# POWER.net
KiCad netlist of a schematic drawn in Altium Designer
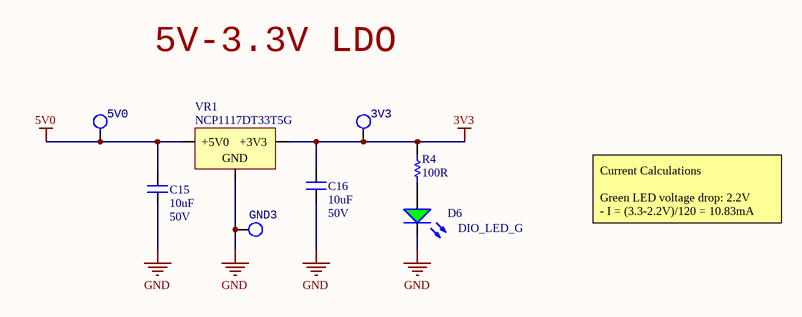
[diagram p0: POWER.SchDoc]

(export (version "E")
  (design (tool "Eeschema 10.0.6"))
  (components
    (comp (ref "3V3")
      (value "TESTPOINT_LOOP")
      (footprint "TESTPOINT_LOOP")
      (description "Loop testpoint through-hole pad")
      (fields (field (name "MANUFACTURER") "Keystone Electronics"))
      (libsource (lib "UWRT_Schematic_Library_2020") (part "TESTPOINT_LOOP"))
    )
    (comp (ref "5V0")
      (value "TESTPOINT_LOOP")
      (footprint "TESTPOINT_LOOP")
      (description "Loop testpoint through-hole pad")
      (fields (field (name "MANUFACTURER") "Keystone Electronics"))
      (libsource (lib "UWRT_Schematic_Library_2020") (part "TESTPOINT_LOOP"))
    )
    (comp (ref "C15")
      (value "10uF")
      (footprint "CAPC1206(3216)")
      (description "CAP CER 10UF 50V X5R 1206")
      (fields
        (field (name "MPN") "GRT31CR61H106KE01L")
        (field (name "MANUFACTURER") "Murata")
        (field (name "VOLTAGE RATING") "50V")
      )
      (libsource (lib "UWRT_Schematic_Library_2020") (part "CAP_10uF_50V_1206"))
    )
    (comp (ref "C16")
      (value "10uF")
      (footprint "CAPC1206(3216)")
      (description "CAP CER 10UF 50V X5R 1206")
      (fields
        (field (name "MPN") "GRT31CR61H106KE01L")
        (field (name "MANUFACTURER") "Murata")
        (field (name "VOLTAGE RATING") "50V")
      )
      (libsource (lib "UWRT_Schematic_Library_2020") (part "CAP_10uF_50V_1206"))
    )
    (comp (ref "D6")
      (value "DIO_LED_G")
      (footprint "LED_0805_LINE")
      (description "LED GREEN DIFFUSED 0805 SMD")
      (fields (field (name "MPN") "LG R971-KN-1") (field (name "MANUFACTURER") "OSRAM"))
      (libsource (lib "UWRT_Schematic_Library_2020") (part "DIO_LED_G"))
    )
    (comp (ref "GND3")
      (value "TESTPOINT_LOOP")
      (footprint "TESTPOINT_LOOP")
      (description "Loop testpoint through-hole pad")
      (fields (field (name "MANUFACTURER") "Keystone Electronics"))
      (libsource (lib "UWRT_Schematic_Library_2020") (part "TESTPOINT_LOOP"))
    )
    (comp (ref "R4")
      (value "100R")
      (footprint "RESC0603(1608)_N")
      (description "RES SMD 100 OHM 1% 1/10W 0603")
      (fields (field (name "MANUFACTURER") "Yageo") (field (name "MPN") "RC0603FR-07100RL"))
      (libsource (lib "UWRT_Schematic_Library_2020") (part "RES_100R_0603"))
    )
    (comp (ref "VR1")
      (value "5V0_3V3_LDO")
      (footprint "VOLTAGE_REGULATOR")
      (description "IC REG LINEAR 3.3V 1A DPAK")
      (fields (field (name "MPN") "NCP1117DT33T5G") (field (name "MANUFACTURER") "ON Semiconductor"))
      (libsource (lib "UWRT_Schematic_Library_2020") (part "5V0_3V3_LDO"))
    )
  )
  (nets
    (net (code "1") (name "3V3") (class "Default")
      (node (ref "3V3") (pin "1") (pintype "passive"))
      (node (ref "C16") (pin "1") (pinfunction "1_1") (pintype "passive"))
      (node (ref "R4") (pin "2") (pinfunction "2_2") (pintype "passive"))
      (node (ref "VR1") (pin "2") (pinfunction "+3V3_2") (pintype "passive"))
    )
    (net (code "2") (name "5V0") (class "Default")
      (node (ref "5V0") (pin "1") (pintype "passive"))
      (node (ref "C15") (pin "1") (pinfunction "1_1") (pintype "passive"))
      (node (ref "VR1") (pin "3") (pinfunction "+5V0_3") (pintype "passive"))
    )
    (net (code "3") (name "GND") (class "Default")
      (node (ref "C15") (pin "2") (pinfunction "2_2") (pintype "passive"))
      (node (ref "C16") (pin "2") (pinfunction "2_2") (pintype "passive"))
      (node (ref "D6") (pin "2") (pinfunction "K_2") (pintype "passive"))
      (node (ref "GND3") (pin "1") (pintype "passive"))
      (node (ref "VR1") (pin "1") (pinfunction "GND_1") (pintype "passive"))
    )
    (net (code "4") (name "Net-(D6-A)") (class "Default")
      (node (ref "D6") (pin "1") (pinfunction "A_1") (pintype "passive"))
      (node (ref "R4") (pin "1") (pinfunction "1_1") (pintype "passive"))
    )
  )
)
